# display-board.net
KiCad netlist of a schematic drawn in EAGLE
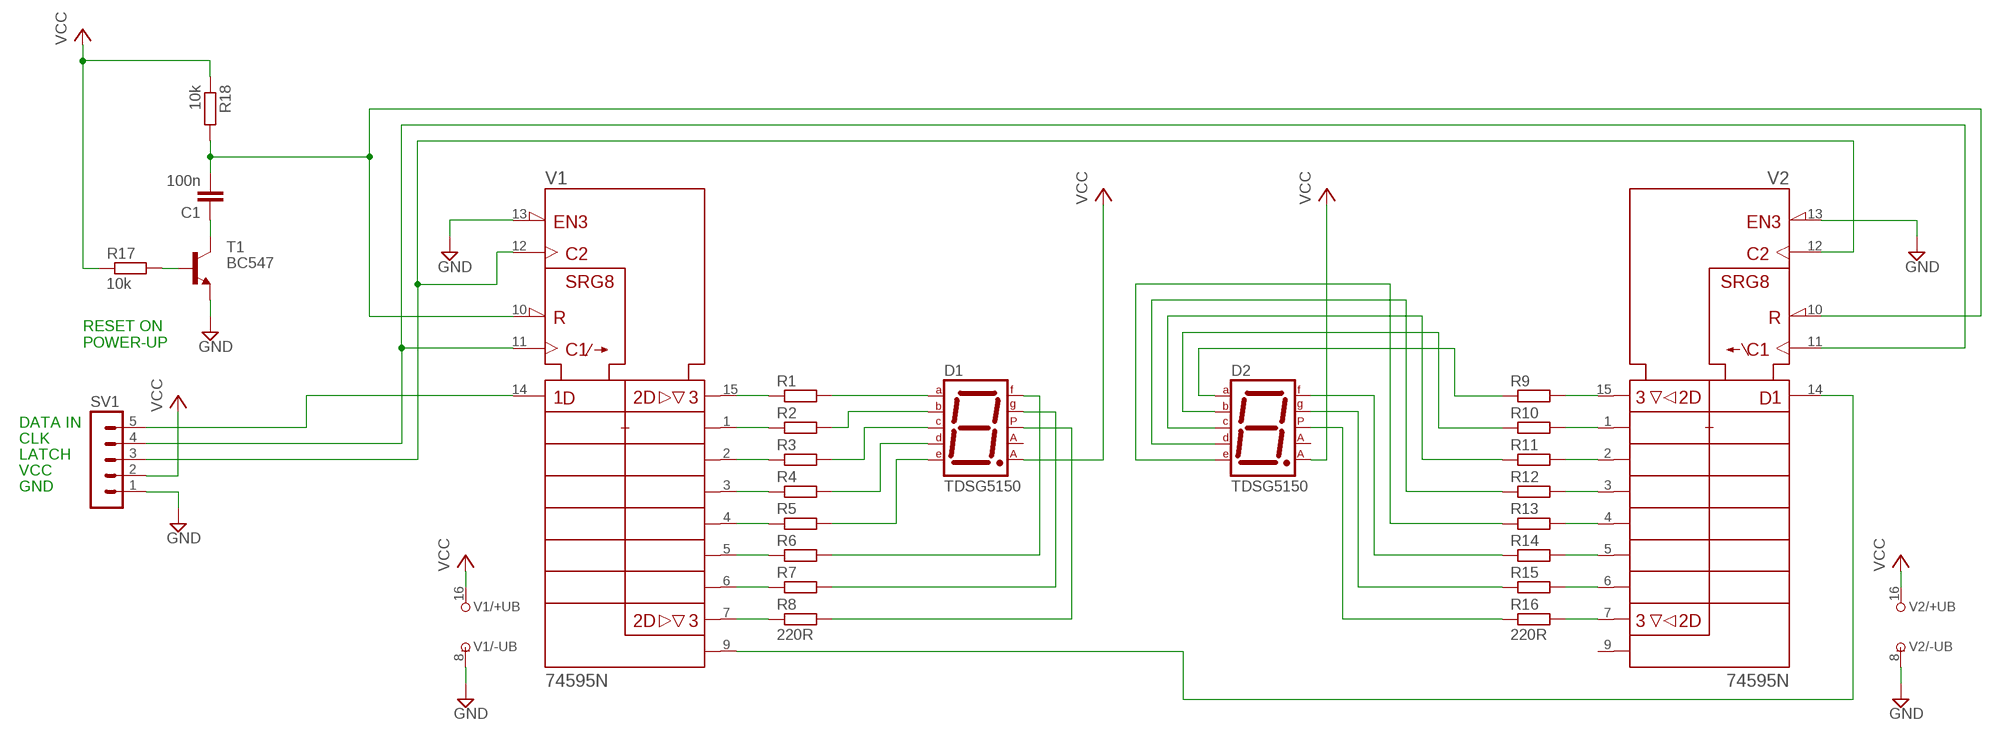
[diagram p0: schematic, sheet 1]

(export (version "E")
  (design (tool "Eeschema 10.0.6"))
  (components
    (comp (ref "C1")
      (value "100n")
      (footprint "eagle-import:C050-024X044")
      (libsource (lib "eagle-import") (part "C-EU050-024X044"))
    )
    (comp (ref "D1")
      (value "TDSG5150")
      (footprint "eagle-import:7SEG-13")
      (libsource (lib "eagle-import") (part "7SEG-CA"))
    )
    (comp (ref "D2")
      (value "TDSG5150")
      (footprint "eagle-import:7SEG-13")
      (libsource (lib "eagle-import") (part "7SEG-CA"))
    )
    (comp (ref "R1")
      (value "R-EU_0207/7")
      (footprint "eagle-import:0207_7")
      (libsource (lib "eagle-import") (part "R-EU_0207/7"))
    )
    (comp (ref "R2")
      (value "R-EU_0207/7")
      (footprint "eagle-import:0207_7")
      (libsource (lib "eagle-import") (part "R-EU_0207/7"))
    )
    (comp (ref "R3")
      (value "R-EU_0207/7")
      (footprint "eagle-import:0207_7")
      (libsource (lib "eagle-import") (part "R-EU_0207/7"))
    )
    (comp (ref "R4")
      (value "R-EU_0207/7")
      (footprint "eagle-import:0207_7")
      (libsource (lib "eagle-import") (part "R-EU_0207/7"))
    )
    (comp (ref "R5")
      (value "R-EU_0207/7")
      (footprint "eagle-import:0207_7")
      (libsource (lib "eagle-import") (part "R-EU_0207/7"))
    )
    (comp (ref "R6")
      (value "R-EU_0207/7")
      (footprint "eagle-import:0207_7")
      (libsource (lib "eagle-import") (part "R-EU_0207/7"))
    )
    (comp (ref "R7")
      (value "R-EU_0207/7")
      (footprint "eagle-import:0207_7")
      (libsource (lib "eagle-import") (part "R-EU_0207/7"))
    )
    (comp (ref "R8")
      (value "220R")
      (footprint "eagle-import:0207_7")
      (libsource (lib "eagle-import") (part "R-EU_0207/7"))
    )
    (comp (ref "R9")
      (value "R-EU_0207/7")
      (footprint "eagle-import:0207_7")
      (libsource (lib "eagle-import") (part "R-EU_0207/7"))
    )
    (comp (ref "R10")
      (value "R-EU_0207/7")
      (footprint "eagle-import:0207_7")
      (libsource (lib "eagle-import") (part "R-EU_0207/7"))
    )
    (comp (ref "R11")
      (value "R-EU_0207/7")
      (footprint "eagle-import:0207_7")
      (libsource (lib "eagle-import") (part "R-EU_0207/7"))
    )
    (comp (ref "R12")
      (value "R-EU_0207/7")
      (footprint "eagle-import:0207_7")
      (libsource (lib "eagle-import") (part "R-EU_0207/7"))
    )
    (comp (ref "R13")
      (value "R-EU_0207/7")
      (footprint "eagle-import:0207_7")
      (libsource (lib "eagle-import") (part "R-EU_0207/7"))
    )
    (comp (ref "R14")
      (value "R-EU_0207/7")
      (footprint "eagle-import:0207_7")
      (libsource (lib "eagle-import") (part "R-EU_0207/7"))
    )
    (comp (ref "R15")
      (value "R-EU_0207/7")
      (footprint "eagle-import:0207_7")
      (libsource (lib "eagle-import") (part "R-EU_0207/7"))
    )
    (comp (ref "R16")
      (value "220R")
      (footprint "eagle-import:0207_7")
      (libsource (lib "eagle-import") (part "R-EU_0207/7"))
    )
    (comp (ref "R17")
      (value "10k")
      (footprint "eagle-import:0207_7")
      (libsource (lib "eagle-import") (part "R-EU_0207/7"))
    )
    (comp (ref "R18")
      (value "10k")
      (footprint "eagle-import:0207_7")
      (libsource (lib "eagle-import") (part "R-EU_0207/7"))
    )
    (comp (ref "SV1")
      (value "MA05-1")
      (footprint "eagle-import:MA05-1")
      (libsource (lib "eagle-import") (part "MA05-1"))
    )
    (comp (ref "T1")
      (value "BC547")
      (footprint "eagle-import:TO92")
      (libsource (lib "eagle-import") (part "BC547"))
    )
    (comp (ref "V1")
      (value "74595N")
      (footprint "eagle-import:DIL16")
      (libsource (lib "eagle-import") (part "74595N"))
    )
    (comp (ref "V2")
      (value "74595N")
      (footprint "eagle-import:DIL16")
      (libsource (lib "eagle-import") (part "74595N"))
    )
  )
  (nets
    (net (code "1") (name "GND") (class "Default")
      (node (ref "SV1") (pin "1") (pinfunction "1_1") (pintype "passive"))
      (node (ref "T1") (pin "1") (pinfunction "E_1") (pintype "passive"))
      (node (ref "V1") (pin "13") (pinfunction "~{G}_13") (pintype "input"))
      (node (ref "V1") (pin "8") (pinfunction "-UB_8") (pintype "power_in"))
      (node (ref "V2") (pin "13") (pinfunction "~{G}_13") (pintype "input"))
      (node (ref "V2") (pin "8") (pinfunction "-UB_8") (pintype "power_in"))
    )
    (net (code "2") (name "Net-(D1-A)") (class "Default")
      (node (ref "D1") (pin "7") (pinfunction "A_7") (pintype "passive"))
      (node (ref "R1") (pin "2") (pinfunction "2_2") (pintype "passive"))
    )
    (net (code "3") (name "Net-(D1-B)") (class "Default")
      (node (ref "D1") (pin "6") (pinfunction "B_6") (pintype "passive"))
      (node (ref "R2") (pin "2") (pinfunction "2_2") (pintype "passive"))
    )
    (net (code "4") (name "Net-(D1-C)") (class "Default")
      (node (ref "D1") (pin "4") (pinfunction "C_4") (pintype "passive"))
      (node (ref "R3") (pin "2") (pinfunction "2_2") (pintype "passive"))
    )
    (net (code "5") (name "Net-(D1-D)") (class "Default")
      (node (ref "D1") (pin "2") (pinfunction "D_2") (pintype "passive"))
      (node (ref "R4") (pin "2") (pinfunction "2_2") (pintype "passive"))
    )
    (net (code "6") (name "Net-(D1-DP)") (class "Default")
      (node (ref "D1") (pin "5") (pinfunction "DP_5") (pintype "passive"))
      (node (ref "R8") (pin "2") (pinfunction "2_2") (pintype "passive"))
    )
    (net (code "7") (name "Net-(D1-E)") (class "Default")
      (node (ref "D1") (pin "1") (pinfunction "E_1") (pintype "passive"))
      (node (ref "R5") (pin "2") (pinfunction "2_2") (pintype "passive"))
    )
    (net (code "8") (name "Net-(D1-F)") (class "Default")
      (node (ref "D1") (pin "9") (pinfunction "F_9") (pintype "passive"))
      (node (ref "R6") (pin "2") (pinfunction "2_2") (pintype "passive"))
    )
    (net (code "9") (name "Net-(D1-G)") (class "Default")
      (node (ref "D1") (pin "10") (pinfunction "G_10") (pintype "passive"))
      (node (ref "R7") (pin "2") (pinfunction "2_2") (pintype "passive"))
    )
    (net (code "10") (name "Net-(D2-A)") (class "Default")
      (node (ref "D2") (pin "7") (pinfunction "A_7") (pintype "passive"))
      (node (ref "R9") (pin "1") (pinfunction "1_1") (pintype "passive"))
    )
    (net (code "11") (name "Net-(D2-B)") (class "Default")
      (node (ref "D2") (pin "6") (pinfunction "B_6") (pintype "passive"))
      (node (ref "R10") (pin "1") (pinfunction "1_1") (pintype "passive"))
    )
    (net (code "12") (name "Net-(D2-C)") (class "Default")
      (node (ref "D2") (pin "4") (pinfunction "C_4") (pintype "passive"))
      (node (ref "R11") (pin "1") (pinfunction "1_1") (pintype "passive"))
    )
    (net (code "13") (name "Net-(D2-D)") (class "Default")
      (node (ref "D2") (pin "2") (pinfunction "D_2") (pintype "passive"))
      (node (ref "R12") (pin "1") (pinfunction "1_1") (pintype "passive"))
    )
    (net (code "14") (name "Net-(D2-DP)") (class "Default")
      (node (ref "D2") (pin "5") (pinfunction "DP_5") (pintype "passive"))
      (node (ref "R16") (pin "1") (pinfunction "1_1") (pintype "passive"))
    )
    (net (code "15") (name "Net-(D2-E)") (class "Default")
      (node (ref "D2") (pin "1") (pinfunction "E_1") (pintype "passive"))
      (node (ref "R13") (pin "1") (pinfunction "1_1") (pintype "passive"))
    )
    (net (code "16") (name "Net-(D2-F)") (class "Default")
      (node (ref "D2") (pin "9") (pinfunction "F_9") (pintype "passive"))
      (node (ref "R14") (pin "1") (pinfunction "1_1") (pintype "passive"))
    )
    (net (code "17") (name "Net-(D2-G)") (class "Default")
      (node (ref "D2") (pin "10") (pinfunction "G_10") (pintype "passive"))
      (node (ref "R15") (pin "1") (pinfunction "1_1") (pintype "passive"))
    )
    (net (code "18") (name "Net-(T1-B)") (class "Default")
      (node (ref "R17") (pin "2") (pinfunction "2_2") (pintype "passive"))
      (node (ref "T1") (pin "2") (pinfunction "B_2") (pintype "passive"))
    )
    (net (code "19") (name "Net-(T1-C)") (class "Default")
      (node (ref "C1") (pin "1") (pinfunction "1_1") (pintype "passive"))
      (node (ref "T1") (pin "3") (pinfunction "C_3") (pintype "passive"))
    )
    (net (code "20") (name "Net-(V1C-QA)") (class "Default")
      (node (ref "R1") (pin "1") (pinfunction "1_1") (pintype "passive"))
      (node (ref "V1") (pin "15") (pinfunction "QA_15") (pintype "tri_state"))
    )
    (net (code "21") (name "Net-(V1C-QB)") (class "Default")
      (node (ref "R2") (pin "1") (pinfunction "1_1") (pintype "passive"))
      (node (ref "V1") (pin "1") (pinfunction "QB_1") (pintype "tri_state"))
    )
    (net (code "22") (name "Net-(V1C-QC)") (class "Default")
      (node (ref "R3") (pin "1") (pinfunction "1_1") (pintype "passive"))
      (node (ref "V1") (pin "2") (pinfunction "QC_2") (pintype "tri_state"))
    )
    (net (code "23") (name "Net-(V1C-QD)") (class "Default")
      (node (ref "R4") (pin "1") (pinfunction "1_1") (pintype "passive"))
      (node (ref "V1") (pin "3") (pinfunction "QD_3") (pintype "tri_state"))
    )
    (net (code "24") (name "Net-(V1C-QE)") (class "Default")
      (node (ref "R5") (pin "1") (pinfunction "1_1") (pintype "passive"))
      (node (ref "V1") (pin "4") (pinfunction "QE_4") (pintype "tri_state"))
    )
    (net (code "25") (name "Net-(V1C-QF)") (class "Default")
      (node (ref "R6") (pin "1") (pinfunction "1_1") (pintype "passive"))
      (node (ref "V1") (pin "5") (pinfunction "QF_5") (pintype "tri_state"))
    )
    (net (code "26") (name "Net-(V1C-QG)") (class "Default")
      (node (ref "R7") (pin "1") (pinfunction "1_1") (pintype "passive"))
      (node (ref "V1") (pin "6") (pinfunction "QG_6") (pintype "tri_state"))
    )
    (net (code "27") (name "Net-(V1C-QH)") (class "Default")
      (node (ref "R8") (pin "1") (pinfunction "1_1") (pintype "passive"))
      (node (ref "V1") (pin "7") (pinfunction "QH_7") (pintype "tri_state"))
    )
    (net (code "28") (name "Net-(V1C-QH*)") (class "Default")
      (node (ref "V1") (pin "9") (pinfunction "QH*_9") (pintype "output"))
      (node (ref "V2") (pin "14") (pinfunction "SER_14") (pintype "input"))
    )
    (net (code "29") (name "Net-(V1C-RCK)") (class "Default")
      (node (ref "SV1") (pin "3") (pinfunction "3_3") (pintype "passive"))
      (node (ref "V1") (pin "12") (pinfunction "RCK_12") (pintype "input"))
      (node (ref "V2") (pin "12") (pinfunction "RCK_12") (pintype "input"))
    )
    (net (code "30") (name "Net-(V1C-SER)") (class "Default")
      (node (ref "SV1") (pin "5") (pinfunction "5_5") (pintype "passive"))
      (node (ref "V1") (pin "14") (pinfunction "SER_14") (pintype "input"))
    )
    (net (code "31") (name "Net-(V1C-SRCK)") (class "Default")
      (node (ref "SV1") (pin "4") (pinfunction "4_4") (pintype "passive"))
      (node (ref "V1") (pin "11") (pinfunction "SRCK_11") (pintype "input"))
      (node (ref "V2") (pin "11") (pinfunction "SRCK_11") (pintype "input"))
    )
    (net (code "32") (name "Net-(V1C-~{SRCLR})") (class "Default")
      (node (ref "C1") (pin "2") (pinfunction "2_2") (pintype "passive"))
      (node (ref "R18") (pin "2") (pinfunction "2_2") (pintype "passive"))
      (node (ref "V1") (pin "10") (pinfunction "~{SRCLR}_10") (pintype "input"))
      (node (ref "V2") (pin "10") (pinfunction "~{SRCLR}_10") (pintype "input"))
    )
    (net (code "33") (name "Net-(V2C-QA)") (class "Default")
      (node (ref "R9") (pin "2") (pinfunction "2_2") (pintype "passive"))
      (node (ref "V2") (pin "15") (pinfunction "QA_15") (pintype "tri_state"))
    )
    (net (code "34") (name "Net-(V2C-QB)") (class "Default")
      (node (ref "R10") (pin "2") (pinfunction "2_2") (pintype "passive"))
      (node (ref "V2") (pin "1") (pinfunction "QB_1") (pintype "tri_state"))
    )
    (net (code "35") (name "Net-(V2C-QC)") (class "Default")
      (node (ref "R11") (pin "2") (pinfunction "2_2") (pintype "passive"))
      (node (ref "V2") (pin "2") (pinfunction "QC_2") (pintype "tri_state"))
    )
    (net (code "36") (name "Net-(V2C-QD)") (class "Default")
      (node (ref "R12") (pin "2") (pinfunction "2_2") (pintype "passive"))
      (node (ref "V2") (pin "3") (pinfunction "QD_3") (pintype "tri_state"))
    )
    (net (code "37") (name "Net-(V2C-QE)") (class "Default")
      (node (ref "R13") (pin "2") (pinfunction "2_2") (pintype "passive"))
      (node (ref "V2") (pin "4") (pinfunction "QE_4") (pintype "tri_state"))
    )
    (net (code "38") (name "Net-(V2C-QF)") (class "Default")
      (node (ref "R14") (pin "2") (pinfunction "2_2") (pintype "passive"))
      (node (ref "V2") (pin "5") (pinfunction "QF_5") (pintype "tri_state"))
    )
    (net (code "39") (name "Net-(V2C-QG)") (class "Default")
      (node (ref "R15") (pin "2") (pinfunction "2_2") (pintype "passive"))
      (node (ref "V2") (pin "6") (pinfunction "QG_6") (pintype "tri_state"))
    )
    (net (code "40") (name "Net-(V2C-QH)") (class "Default")
      (node (ref "R16") (pin "2") (pinfunction "2_2") (pintype "passive"))
      (node (ref "V2") (pin "7") (pinfunction "QH_7") (pintype "tri_state"))
    )
    (net (code "41") (name "VCC") (class "Default")
      (node (ref "D1") (pin "8") (pinfunction "CA2_8") (pintype "passive"))
      (node (ref "D2") (pin "8") (pinfunction "CA2_8") (pintype "passive"))
      (node (ref "R17") (pin "1") (pinfunction "1_1") (pintype "passive"))
      (node (ref "R18") (pin "1") (pinfunction "1_1") (pintype "passive"))
      (node (ref "SV1") (pin "2") (pinfunction "2_2") (pintype "passive"))
      (node (ref "V1") (pin "16") (pinfunction "+UB_16") (pintype "power_in"))
      (node (ref "V2") (pin "16") (pinfunction "+UB_16") (pintype "power_in"))
    )
    (net (code "42") (name "unconnected-(D1-CA1-Pad3)") (class "Default")
      (node (ref "D1") (pin "3") (pinfunction "CA1_3") (pintype "passive"))
    )
    (net (code "43") (name "unconnected-(D2-CA1-Pad3)") (class "Default")
      (node (ref "D2") (pin "3") (pinfunction "CA1_3") (pintype "passive"))
    )
    (net (code "44") (name "unconnected-(V2C-QH*-Pad9)") (class "Default")
      (node (ref "V2") (pin "9") (pinfunction "QH*_9") (pintype "output"))
    )
  )
)
